# Power.net
KiCad netlist of a schematic drawn in Altium Designer
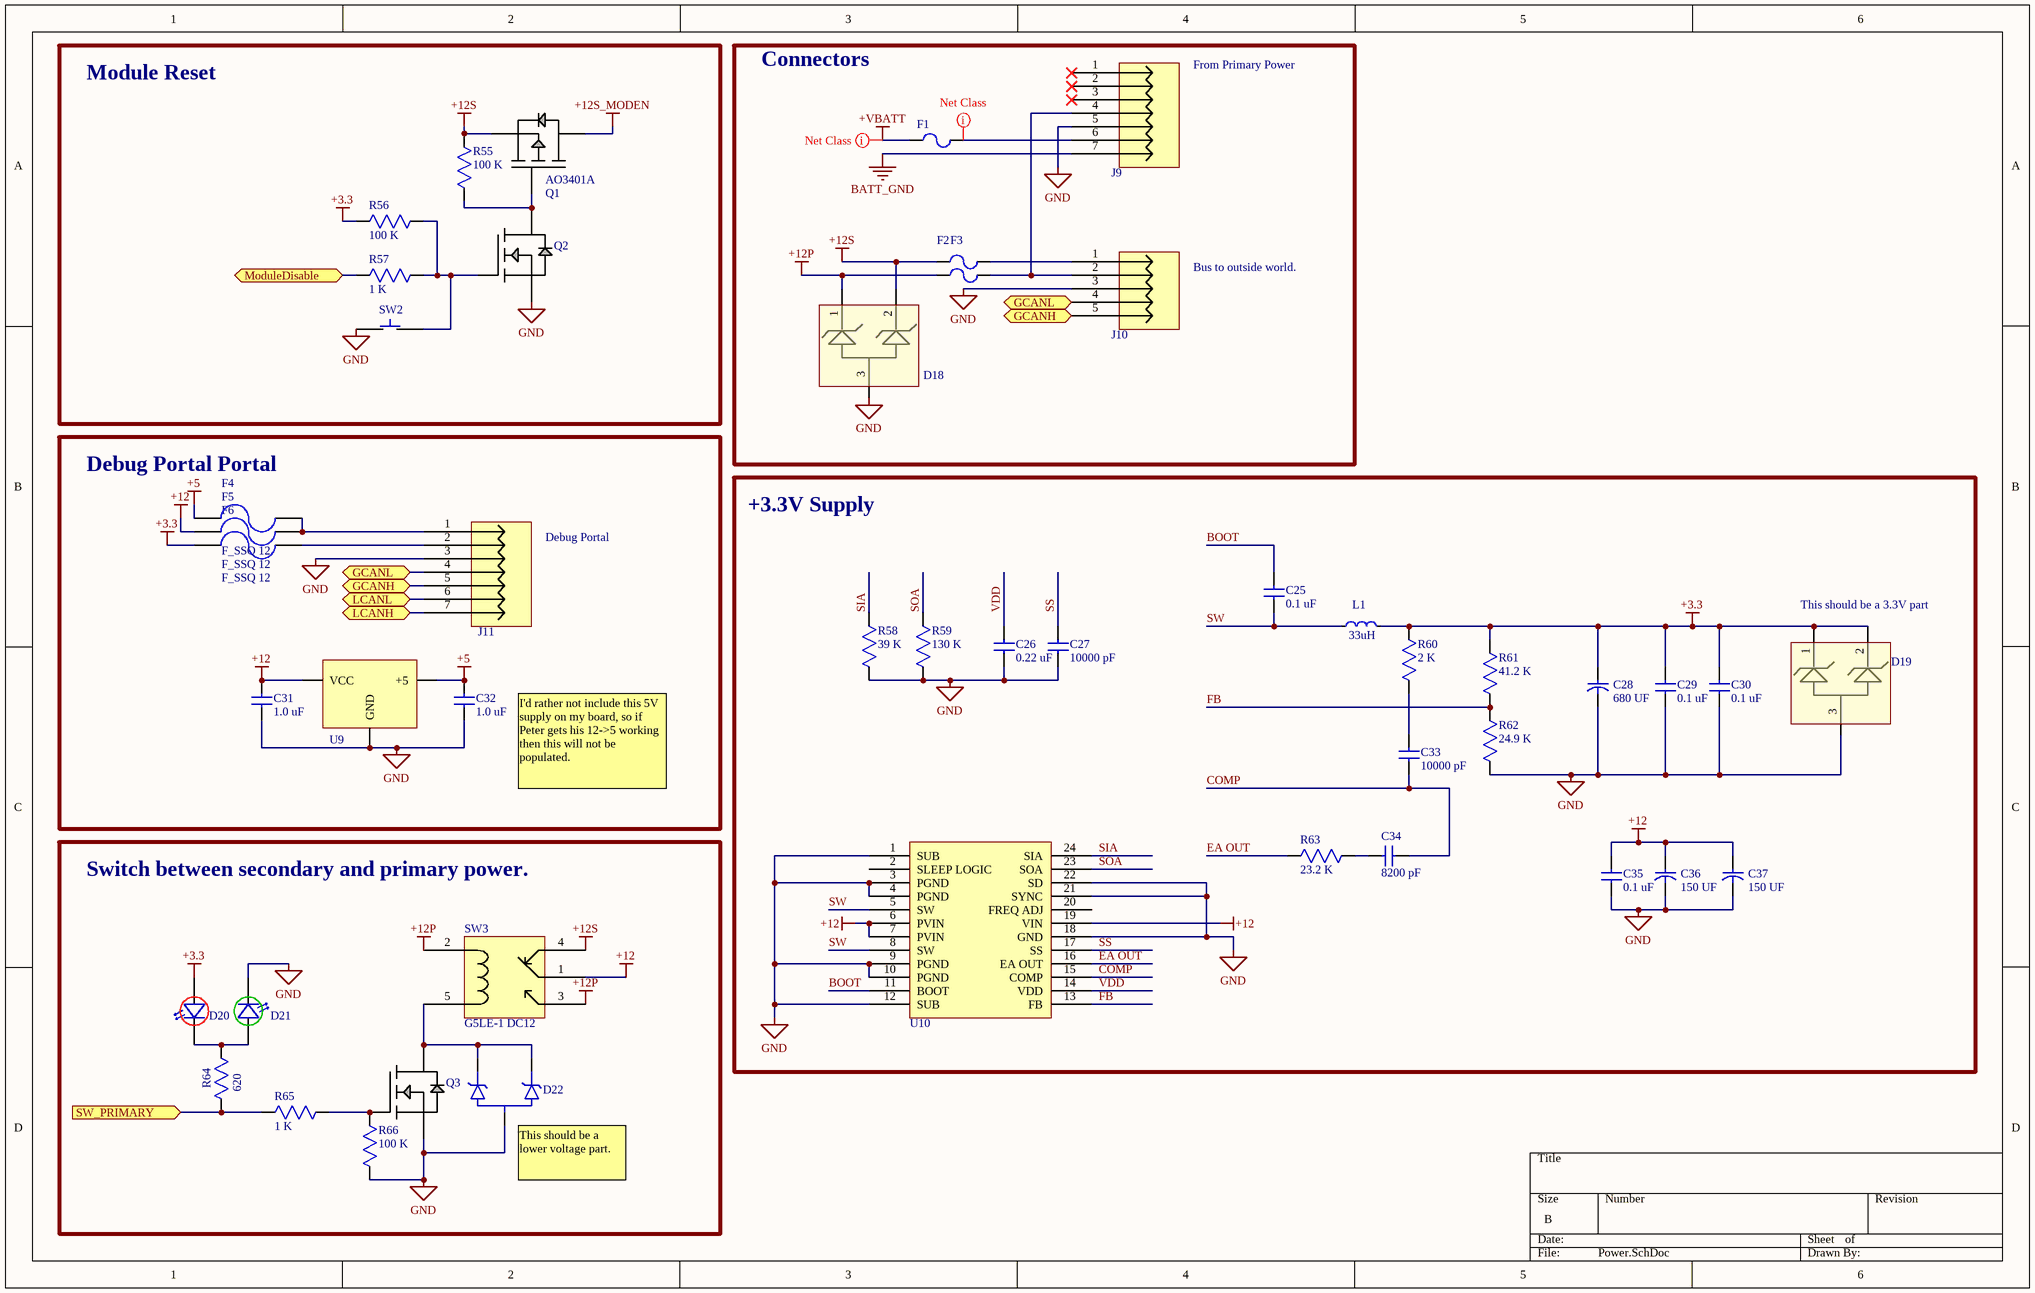
[diagram p0: Power.SchDoc]

(export (version "E")
  (design (tool "Eeschema 10.0.6"))
  (components
    (comp (ref "C25")
      (value "0.1 uF")
      (footprint "0603_cap")
      (description "CAP CERM 0603")
      (fields (field (name "Comment") "CAP 0603"))
      (libsource (lib "Nutz") (part "C_0603"))
    )
    (comp (ref "C26")
      (value "0.22 uF")
      (footprint "0603_cap")
      (description "CAP CERM 0603")
      (fields (field (name "Comment") "CAP 0603"))
      (libsource (lib "Nutz") (part "C_0603"))
    )
    (comp (ref "C27")
      (value "10000 pF")
      (footprint "0603_cap")
      (description "CAP CERM 0603")
      (fields (field (name "Comment") "CAP 0603"))
      (libsource (lib "Nutz") (part "C_0603"))
    )
    (comp (ref "C28")
      (value "680 UF")
      (footprint "CAP_NICHICON_R7")
      (description "CAP POLY 680UF 10V LOW ESR RAD")
      (fields
        (field (name "MANUFACTURER") "Nichicon")
        (field (name "Comment") "CAP POLY 680UF")
        (field (name "SVP CREATOR") "Jonathan Nutzmann")
      )
      (libsource (lib "c3_SchLib") (part "C_POLY_680UF_10V"))
    )
    (comp (ref "C29")
      (value "0.1 uF")
      (footprint "0603_cap")
      (description "CAP CERM 0603")
      (fields (field (name "Comment") "CAP 0603"))
      (libsource (lib "Nutz") (part "C_0603"))
    )
    (comp (ref "C30")
      (value "0.1 uF")
      (footprint "0603_cap")
      (description "CAP CERM 0603")
      (fields (field (name "Comment") "CAP 0603"))
      (libsource (lib "Nutz") (part "C_0603"))
    )
    (comp (ref "C31")
      (value "1.0 uF")
      (footprint "0805_Capacitor")
      (description "CAP CERM 1uF")
      (fields (field (name "Comment") "CAP 1uF") (field (name "SVP CREATOR") "Mark Newcomb"))
      (libsource (lib "c3_SchLib") (part "C_0805_1.0uF"))
    )
    (comp (ref "C32")
      (value "1.0 uF")
      (footprint "0805_Capacitor")
      (description "CAP CERM 1uF")
      (fields (field (name "Comment") "CAP 1uF") (field (name "SVP CREATOR") "Mark Newcomb"))
      (libsource (lib "c3_SchLib") (part "C_0805_1.0uF"))
    )
    (comp (ref "C33")
      (value "10000 pF")
      (footprint "0603_cap")
      (description "CAP CERM 0603")
      (fields (field (name "Comment") "CAP 0603"))
      (libsource (lib "Nutz") (part "C_0603"))
    )
    (comp (ref "C34")
      (value "8200 pF")
      (footprint "0603_cap")
      (description "CAP CERM 0603")
      (fields (field (name "Comment") "CAP 0603"))
      (libsource (lib "Nutz") (part "C_0603"))
    )
    (comp (ref "C35")
      (value "0.1 uF")
      (footprint "0603_cap")
      (description "CAP CERM 0603")
      (fields (field (name "Comment") "CAP 0603"))
      (libsource (lib "Nutz") (part "C_0603"))
    )
    (comp (ref "C36")
      (value "150 UF")
      (footprint "CAP_NICHICON_R7")
      (description "CAP POLY 150UF 20V HT 125C RAD")
      (fields
        (field (name "MANUFACTURER") "Nichicon")
        (field (name "TOLERANCE") "20%")
        (field (name "SVP CREATOR") "Jonathan Nutzmann")
      )
      (libsource (lib "c3_SchLib") (part "C_POLY_150UF"))
    )
    (comp (ref "C37")
      (value "150 UF")
      (footprint "CAP_NICHICON_R7")
      (description "CAP POLY 150UF 20V HT 125C RAD")
      (fields
        (field (name "MANUFACTURER") "Nichicon")
        (field (name "TOLERANCE") "20%")
        (field (name "SVP CREATOR") "Jonathan Nutzmann")
      )
      (libsource (lib "c3_SchLib") (part "C_POLY_150UF"))
    )
    (comp (ref "D18")
      (value "SM15.TCT")
      (footprint "SOT-23")
      (description "IC TVS ARRAY 2UNI/1BI 15V SOT-23")
      (fields (field (name "MANUFACTURER") "Semtech") (field (name "SVP CREATOR") "Jonathan Nutzmann"))
      (libsource (lib "c3_SchLib") (part "D_SM15TCT"))
    )
    (comp (ref "D19")
      (value "MMBZ6V8AL,215")
      (footprint "SOT-23")
      (description "DIODE ESD PROT DBL 4.5V SOT23")
      (fields (field (name "MANUFACTURER") "NXP") (field (name "SVP CREATOR") "Jonathan Nutzmann"))
      (libsource (lib "c3_SchLib") (part "D_MMBZ6V8AL,215"))
    )
    (comp (ref "D20")
      (value "D_LED_0805_RED")
      (footprint "0805P_RED")
      (description "LED CHIPLED 645NM RED DIFF 0805")
      (fields (field (name "SVP CREATOR") "Jonathan Nutzmann"))
      (libsource (lib "c3_SchLib") (part "D_LED_0805_RED"))
    )
    (comp (ref "D21")
      (value "D_LED_0805_GREEN")
      (footprint "0805P_Green")
      (description "LED CHIPLED 570NM GREEN 0805 SMD")
      (fields
        (field (name "MANUFACTURER") "Osram Opto Semiconductors Inc")
        (field (name "SVP CREATOR") "Nate Bolyard")
        (field (name "SVP REVIEWER 1") "Trevtron")
      )
      (libsource (lib "c3_SchLib") (part "D_LED_0805_GREEN"))
    )
    (comp (ref "D22")
      (value "D_AZ23C36-TP")
      (footprint "SOT-23")
      (description "DIODE ZENER DUAL 36V SOT-23")
      (fields (field (name "MANUFACTURER") "Micro") (field (name "SVP CREATOR") "Jonathan Nutzmann"))
      (libsource (lib "c3_SchLib") (part "D_AZ23C36-TP"))
    )
    (comp (ref "F1")
      (value "F_3101.0040")
      (footprint "FPG4 Fuseholder")
      (description "Schurter FPG4 5mm x 20mm Fuse Holder")
      (libsource (lib "c3_SchLib") (part "F_3101.0040"))
    )
    (comp (ref "F2")
      (value "F_3101.0040")
      (footprint "FPG4 Fuseholder")
      (description "Schurter FPG4 5mm x 20mm Fuse Holder")
      (libsource (lib "c3_SchLib") (part "F_3101.0040"))
    )
    (comp (ref "F3")
      (value "F_3101.0040")
      (footprint "FPG4 Fuseholder")
      (description "Schurter FPG4 5mm x 20mm Fuse Holder")
      (libsource (lib "c3_SchLib") (part "F_3101.0040"))
    )
    (comp (ref "F4")
      (value "F_SSQ 12")
      (footprint "2410")
      (description "FUSE 12A 125V 6125 FAST SSQ")
      (fields
        (field (name "MANUFACTURER") "Bel Fuse Inc")
        (field (name "SVN CREATOR") "Nate Bolyard")
        (field (name "SVN REVIEWER 2") "*")
      )
      (libsource (lib "c3_SchLib") (part "F_SSQ 12"))
    )
    (comp (ref "F5")
      (value "F_SSQ 12")
      (footprint "2410")
      (description "FUSE 12A 125V 6125 FAST SSQ")
      (fields
        (field (name "MANUFACTURER") "Bel Fuse Inc")
        (field (name "SVN CREATOR") "Nate Bolyard")
        (field (name "SVN REVIEWER 2") "*")
      )
      (libsource (lib "c3_SchLib") (part "F_SSQ 12"))
    )
    (comp (ref "F6")
      (value "F_SSQ 12")
      (footprint "2410")
      (description "FUSE 12A 125V 6125 FAST SSQ")
      (fields
        (field (name "MANUFACTURER") "Bel Fuse Inc")
        (field (name "SVN CREATOR") "Nate Bolyard")
        (field (name "SVN REVIEWER 2") "*")
      )
      (libsource (lib "c3_SchLib") (part "F_SSQ 12"))
    )
    (comp (ref "J9")
      (value "J_PHOENIX_7M_5.08")
      (footprint "PHONEIX_7_5.08")
      (description "7 Pin Male Phoenix Connector 5.08")
      (fields (field (name "SVP CREATOR") "Jonathan Nutzmann"))
      (libsource (lib "c3_SchLib") (part "J_PHOENIX_7M_5.08"))
    )
    (comp (ref "J10")
      (value "J_PHOENIX_5M_3.5")
      (footprint "1843635")
      (description "5 Pin Male Phoenix Connector 3.5")
      (fields (field (name "SVP CREATOR") "Jonathan Nutzmann"))
      (libsource (lib "c3_SchLib") (part "J_PHOENIX_5M_3.5"))
    )
    (comp (ref "J11")
      (value "~")
      (footprint "1843651")
      (description "7 Pin Male Phoenix Connector 3.5")
      (fields (field (name "SVP CREATOR") "Jonathan Nutzmann"))
      (libsource (lib "c3_SchLib") (part "J_PHOENIX_7M_3.5"))
    )
    (comp (ref "L1")
      (value "33uH")
      (footprint "L_SRR1210")
      (description "INDUCTOR PWR 33UH 20% SHIELD SMD")
      (fields
        (field (name "MANUFACTURER") "Bourns Inc")
        (field (name "Comment") "L_33uH_20%")
        (field (name "SVP CREATOR") "Jonathan Nutzmann")
      )
      (libsource (lib "c3_SchLib") (part "L_33uH_20%"))
    )
    (comp (ref "Q1")
      (value "Q_AO3401A")
      (footprint "SOT-23")
      (description "MOSFET P-CH -30V -4.3A SOT23")
      (fields (field (name "MANUFACTURER") "Alpha & Omega") (field (name "MANUFACTURER PN") "AO3401A"))
      (libsource (lib "Nutz") (part "Q_AO3401A"))
    )
    (comp (ref "Q2")
      (value "RK7002BT116")
      (footprint "SOT-23")
      (description "MOSFET N-CH 60V 250MA SOT-23")
      (fields
        (field (name "MANUFACTURER") "Rohm Semiconductor")
        (field (name "SVP CREATOR") "Jonathan Nutzmann")
      )
      (libsource (lib "c3_SchLib") (part "Q_N_60V_250MA_SOT23"))
    )
    (comp (ref "Q3")
      (value "2SK3541T2L")
      (footprint "SOT-23")
      (description "MOSFET N-CH 20V 0.9A SOT-23")
      (fields
        (field (name "MANUFACTURER") "Fairchild Semiconductor")
        (field (name "SVP CREATOR") "Jonathan Nutzmann")
      )
      (libsource (lib "c3_SchLib") (part "Q_2SK3541T2L"))
    )
    (comp (ref "R55")
      (value "100 K")
      (footprint "0603_res")
      (description "RES 0603")
      (libsource (lib "Nutz") (part "R_0603"))
    )
    (comp (ref "R56")
      (value "100 K")
      (footprint "0603_res")
      (description "RES 0603")
      (libsource (lib "Nutz") (part "R_0603"))
    )
    (comp (ref "R57")
      (value "1 K")
      (footprint "0603_res")
      (description "RES 0603")
      (libsource (lib "Nutz") (part "R_0603"))
    )
    (comp (ref "R58")
      (value "39 K")
      (footprint "0603_res")
      (description "RES 0603")
      (libsource (lib "Nutz") (part "R_0603"))
    )
    (comp (ref "R59")
      (value "130 K")
      (footprint "0603_res")
      (description "RES 0603")
      (libsource (lib "Nutz") (part "R_0603"))
    )
    (comp (ref "R60")
      (value "2 K")
      (footprint "0603_res")
      (description "RES 0603")
      (libsource (lib "Nutz") (part "R_0603"))
    )
    (comp (ref "R61")
      (value "41.2 K")
      (footprint "0603_res")
      (description "RES 0603")
      (libsource (lib "Nutz") (part "R_0603"))
    )
    (comp (ref "R62")
      (value "24.9 K")
      (footprint "0603_res")
      (description "RES 0603")
      (libsource (lib "Nutz") (part "R_0603"))
    )
    (comp (ref "R63")
      (value "23.2 K")
      (footprint "0603_res")
      (description "RES 0603")
      (libsource (lib "Nutz") (part "R_0603"))
    )
    (comp (ref "R64")
      (value "620")
      (footprint "0805_Resistor")
      (description "RES 620 OHM 1/8W 1% 0805 SMD")
      (fields (field (name "Comment") "R_0805_620_1%") (field (name "SVP CREATOR") "Jonathan Nutzmann"))
      (libsource (lib "c3_SchLib") (part "R_0805_620_1%"))
    )
    (comp (ref "R65")
      (value "1 K")
      (footprint "0603_res")
      (description "RES 0603")
      (libsource (lib "Nutz") (part "R_0603"))
    )
    (comp (ref "R66")
      (value "100 K")
      (footprint "0603_res")
      (description "RES 0603")
      (libsource (lib "Nutz") (part "R_0603"))
    )
    (comp (ref "SW2")
      (value "SW_TACT_SWITCH_6x6")
      (footprint "TACT_SWITCH_6x6")
      (description "SWITCH TACT 6MM BLACK 160GF")
      (fields (field (name "MANUFACTURER") "Tyco Electronics") (field (name "SVP CREATOR") "Nate Bolyard"))
      (libsource (lib "c3_SchLib") (part "SW_TACT_SWITCH_6x6"))
    )
    (comp (ref "SW3")
      (value "SW_G5LE-1 DC12")
      (footprint "G5LE-1 DC12")
      (description "RELAY GEN PURPOSE SPDT 10A 12V")
      (fields
        (field (name "MANUFACTURER") "Omron")
        (field (name "MANUFACTURER PN") "G5LE-1 DC12")
        (field (name "SVP CREATOR") "Jonathan Nutzmann")
      )
      (libsource (lib "c3_SchLib") (part "SW_G5LE-1 DC12"))
    )
    (comp (ref "U9")
      (value "MC7805BDTG")
      (footprint "DPAK")
      (description "IC REG POS VOLT 1A 5V DPAK")
      (fields
        (field (name "MANUFACTURER") "ON Semiconductor")
        (field (name "SVP CREATOR") "Jonathan Nutzmann")
      )
      (libsource (lib "c3_SchLib") (part "U_MC7805BDTG"))
    )
    (comp (ref "U10")
      (value "LM2650 DC/DC Converter")
      (footprint "SOIC127P1030X265-24N")
      (description "IC CONVERTER SYNCH DC/DC 24-SOIC")
      (fields
        (field (name "MANUFACTURER") "National Semiconductor")
        (field (name "SVP CREATOR") "Jonathan Nutzmann")
      )
      (libsource (lib "c3_SchLib") (part "U_LM2650"))
    )
  )
  (nets
    (net (code "1") (name "+3.3") (class "Default")
      (node (ref "C28") (pin "1") (pinfunction "1_1") (pintype "passive"))
      (node (ref "C29") (pin "1") (pinfunction "1_1") (pintype "passive"))
      (node (ref "C30") (pin "1") (pinfunction "1_1") (pintype "passive"))
      (node (ref "D19") (pin "1") (pintype "passive"))
      (node (ref "D19") (pin "2") (pintype "passive"))
      (node (ref "D20") (pin "2") (pinfunction "Anode_2") (pintype "passive"))
      (node (ref "F6") (pin "1") (pinfunction "1_1") (pintype "passive"))
      (node (ref "L1") (pin "2") (pinfunction "2_2") (pintype "passive"))
      (node (ref "R56") (pin "2") (pinfunction "2_2") (pintype "passive"))
      (node (ref "R60") (pin "1") (pinfunction "1_1") (pintype "passive"))
      (node (ref "R61") (pin "2") (pinfunction "2_2") (pintype "passive"))
    )
    (net (code "2") (name "+5") (class "Default")
      (node (ref "C32") (pin "1") (pinfunction "1_1") (pintype "passive"))
      (node (ref "F4") (pin "1") (pinfunction "1_1") (pintype "passive"))
      (node (ref "U9") (pin "2") (pinfunction "+5_2") (pintype "passive"))
    )
    (net (code "3") (name "+12") (class "Default")
      (node (ref "C31") (pin "1") (pinfunction "1_1") (pintype "passive"))
      (node (ref "C35") (pin "1") (pinfunction "1_1") (pintype "passive"))
      (node (ref "C36") (pin "1") (pinfunction "1_1") (pintype "passive"))
      (node (ref "C37") (pin "1") (pinfunction "1_1") (pintype "passive"))
      (node (ref "F5") (pin "1") (pinfunction "1_1") (pintype "passive"))
      (node (ref "SW3") (pin "1") (pinfunction "1_1") (pintype "passive"))
      (node (ref "U10") (pin "19") (pinfunction "VIN_19") (pintype "passive"))
      (node (ref "U10") (pin "6") (pinfunction "PVIN_6") (pintype "passive"))
      (node (ref "U10") (pin "7") (pinfunction "PVIN_7") (pintype "passive"))
      (node (ref "U9") (pin "3") (pinfunction "VCC_3") (pintype "passive"))
    )
    (net (code "4") (name "+12P") (class "Default")
      (node (ref "D18") (pin "1") (pintype "passive"))
      (node (ref "F3") (pin "1") (pinfunction "1_1") (pintype "passive"))
      (node (ref "SW3") (pin "2") (pinfunction "+_2") (pintype "passive"))
      (node (ref "SW3") (pin "3") (pinfunction "3_3") (pintype "passive"))
    )
    (net (code "5") (name "+12S") (class "Default")
      (node (ref "D18") (pin "2") (pintype "passive"))
      (node (ref "F2") (pin "1") (pinfunction "1_1") (pintype "passive"))
      (node (ref "Q1") (pin "2") (pinfunction "SOURCE_2") (pintype "passive"))
      (node (ref "R55") (pin "2") (pinfunction "2_2") (pintype "passive"))
      (node (ref "SW3") (pin "4") (pinfunction "4_4") (pintype "passive"))
    )
    (net (code "6") (name "+12S_MODEN") (class "Default")
      (node (ref "Q1") (pin "3") (pinfunction "DRAIN_3") (pintype "passive"))
    )
    (net (code "7") (name "+VBATT") (class "Default")
      (node (ref "F1") (pin "1") (pinfunction "1_1") (pintype "passive"))
    )
    (net (code "8") (name "/BOOT") (class "Default")
      (node (ref "C25") (pin "1") (pinfunction "1_1") (pintype "passive"))
      (node (ref "U10") (pin "11") (pinfunction "BOOT_11") (pintype "passive"))
    )
    (net (code "9") (name "/COMP") (class "Default")
      (node (ref "C33") (pin "2") (pinfunction "2_2") (pintype "passive"))
      (node (ref "C34") (pin "2") (pinfunction "2_2") (pintype "passive"))
      (node (ref "U10") (pin "15") (pinfunction "COMP_15") (pintype "passive"))
    )
    (net (code "10") (name "/EA OUT") (class "Default")
      (node (ref "R63") (pin "2") (pinfunction "2_2") (pintype "passive"))
      (node (ref "U10") (pin "16") (pinfunction "EA_OUT_16") (pintype "passive"))
    )
    (net (code "11") (name "/FB") (class "Default")
      (node (ref "R61") (pin "1") (pinfunction "1_1") (pintype "passive"))
      (node (ref "R62") (pin "2") (pinfunction "2_2") (pintype "passive"))
      (node (ref "U10") (pin "13") (pinfunction "FB_13") (pintype "passive"))
    )
    (net (code "12") (name "/GCANH") (class "Default")
      (node (ref "J10") (pin "5") (pinfunction "5_5") (pintype "passive"))
      (node (ref "J11") (pin "5") (pinfunction "5_5") (pintype "passive"))
    )
    (net (code "13") (name "/GCANL") (class "Default")
      (node (ref "J10") (pin "4") (pinfunction "4_4") (pintype "passive"))
      (node (ref "J11") (pin "4") (pinfunction "4_4") (pintype "passive"))
    )
    (net (code "14") (name "/LCANH") (class "Default")
      (node (ref "J11") (pin "7") (pinfunction "7_7") (pintype "passive"))
    )
    (net (code "15") (name "/LCANL") (class "Default")
      (node (ref "J11") (pin "6") (pinfunction "6_6") (pintype "passive"))
    )
    (net (code "16") (name "/ModuleDisable") (class "Default")
      (node (ref "R57") (pin "2") (pinfunction "2_2") (pintype "passive"))
    )
    (net (code "17") (name "/SIA") (class "Default")
      (node (ref "R58") (pin "1") (pinfunction "1_1") (pintype "passive"))
      (node (ref "U10") (pin "24") (pinfunction "SIA_24") (pintype "passive"))
    )
    (net (code "18") (name "/SOA") (class "Default")
      (node (ref "R59") (pin "1") (pinfunction "1_1") (pintype "passive"))
      (node (ref "U10") (pin "23") (pinfunction "SOA_23") (pintype "passive"))
    )
    (net (code "19") (name "/SS") (class "Default")
      (node (ref "C27") (pin "1") (pinfunction "1_1") (pintype "passive"))
      (node (ref "U10") (pin "17") (pinfunction "SS_17") (pintype "passive"))
    )
    (net (code "20") (name "/SW") (class "Default")
      (node (ref "C25") (pin "2") (pinfunction "2_2") (pintype "passive"))
      (node (ref "L1") (pin "1") (pinfunction "1_1") (pintype "passive"))
      (node (ref "U10") (pin "5") (pinfunction "SW_5") (pintype "passive"))
      (node (ref "U10") (pin "8") (pinfunction "SW_8") (pintype "passive"))
    )
    (net (code "21") (name "/SW_PRIMARY") (class "Default")
      (node (ref "R64") (pin "2") (pinfunction "2_2") (pintype "passive"))
      (node (ref "R65") (pin "2") (pinfunction "2_2") (pintype "passive"))
    )
    (net (code "22") (name "/VDD") (class "Default")
      (node (ref "C26") (pin "1") (pinfunction "1_1") (pintype "passive"))
      (node (ref "U10") (pin "14") (pinfunction "VDD_14") (pintype "passive"))
    )
    (net (code "23") (name "BATT_GND") (class "Default")
      (node (ref "J9") (pin "7") (pinfunction "7_7") (pintype "passive"))
    )
    (net (code "24") (name "GND") (class "Default")
      (node (ref "C26") (pin "2") (pinfunction "2_2") (pintype "passive"))
      (node (ref "C27") (pin "2") (pinfunction "2_2") (pintype "passive"))
      (node (ref "C28") (pin "2") (pinfunction "2_2") (pintype "passive"))
      (node (ref "C29") (pin "2") (pinfunction "2_2") (pintype "passive"))
      (node (ref "C30") (pin "2") (pinfunction "2_2") (pintype "passive"))
      (node (ref "C31") (pin "2") (pinfunction "2_2") (pintype "passive"))
      (node (ref "C32") (pin "2") (pinfunction "2_2") (pintype "passive"))
      (node (ref "C35") (pin "2") (pinfunction "2_2") (pintype "passive"))
      (node (ref "C36") (pin "2") (pinfunction "2_2") (pintype "passive"))
      (node (ref "C37") (pin "2") (pinfunction "2_2") (pintype "passive"))
      (node (ref "D18") (pin "3") (pintype "passive"))
      (node (ref "D19") (pin "3") (pintype "passive"))
      (node (ref "D21") (pin "1") (pinfunction "Cathode_1") (pintype "passive"))
      (node (ref "D22") (pin "3") (pinfunction "ANODE_3") (pintype "passive"))
      (node (ref "J10") (pin "3") (pinfunction "3_3") (pintype "passive"))
      (node (ref "J11") (pin "3") (pinfunction "3_3") (pintype "passive"))
      (node (ref "J9") (pin "5") (pinfunction "5_5") (pintype "passive"))
      (node (ref "Q2") (pin "2") (pinfunction "SOURCE_2") (pintype "passive"))
      (node (ref "Q3") (pin "2") (pinfunction "SOURCE_2") (pintype "passive"))
      (node (ref "R58") (pin "2") (pinfunction "2_2") (pintype "passive"))
      (node (ref "R59") (pin "2") (pinfunction "2_2") (pintype "passive"))
      (node (ref "R62") (pin "1") (pinfunction "1_1") (pintype "passive"))
      (node (ref "R66") (pin "1") (pinfunction "1_1") (pintype "passive"))
      (node (ref "SW2") (pin "1") (pinfunction "1_1") (pintype "passive"))
      (node (ref "U10") (pin "1") (pinfunction "SUB_1") (pintype "passive"))
      (node (ref "U10") (pin "10") (pinfunction "PGND_10") (pintype "passive"))
      (node (ref "U10") (pin "12") (pinfunction "SUB_12") (pintype "passive"))
      (node (ref "U10") (pin "18") (pinfunction "GND_18") (pintype "passive"))
      (node (ref "U10") (pin "21") (pinfunction "SYNC_21") (pintype "passive"))
      (node (ref "U10") (pin "22") (pinfunction "SD_22") (pintype "passive"))
      (node (ref "U10") (pin "3") (pinfunction "PGND_3") (pintype "passive"))
      (node (ref "U10") (pin "4") (pinfunction "PGND_4") (pintype "passive"))
      (node (ref "U10") (pin "9") (pinfunction "PGND_9") (pintype "passive"))
      (node (ref "U9") (pin "1") (pinfunction "GND_1") (pintype "passive"))
    )
    (net (code "25") (name "Net-(C33-Pad1)") (class "Default")
      (node (ref "C33") (pin "1") (pinfunction "1_1") (pintype "passive"))
      (node (ref "R60") (pin "2") (pinfunction "2_2") (pintype "passive"))
    )
    (net (code "26") (name "Net-(C34-Pad1)") (class "Default")
      (node (ref "C34") (pin "1") (pinfunction "1_1") (pintype "passive"))
      (node (ref "R63") (pin "1") (pinfunction "1_1") (pintype "passive"))
    )
    (net (code "27") (name "Net-(D20-Cathode)") (class "Default")
      (node (ref "D20") (pin "1") (pinfunction "Cathode_1") (pintype "passive"))
      (node (ref "D21") (pin "2") (pinfunction "Anode_2") (pintype "passive"))
      (node (ref "R64") (pin "1") (pinfunction "1_1") (pintype "passive"))
    )
    (net (code "28") (name "Net-(D22-CATHODE_1)") (class "Default")
      (node (ref "D22") (pin "1") (pinfunction "CATHODE_1_1") (pintype "passive"))
      (node (ref "D22") (pin "2") (pinfunction "CATHODE_2_2") (pintype "passive"))
      (node (ref "Q3") (pin "3") (pinfunction "DRAIN_3") (pintype "passive"))
      (node (ref "SW3") (pin "5") (pinfunction "-_5") (pintype "passive"))
    )
    (net (code "29") (name "Net-(F1-Pad2)") (class "Default")
      (node (ref "F1") (pin "2") (pinfunction "2_2") (pintype "passive"))
      (node (ref "J9") (pin "6") (pinfunction "6_6") (pintype "passive"))
    )
    (net (code "30") (name "Net-(F2-Pad2)") (class "Default")
      (node (ref "F2") (pin "2") (pinfunction "2_2") (pintype "passive"))
      (node (ref "J10") (pin "1") (pinfunction "1_1") (pintype "passive"))
    )
    (net (code "31") (name "Net-(F3-Pad2)") (class "Default")
      (node (ref "F3") (pin "2") (pinfunction "2_2") (pintype "passive"))
      (node (ref "J10") (pin "2") (pinfunction "2_2") (pintype "passive"))
      (node (ref "J9") (pin "4") (pinfunction "4_4") (pintype "passive"))
    )
    (net (code "32") (name "Net-(F4-Pad2)") (class "Default")
      (node (ref "F4") (pin "2") (pinfunction "2_2") (pintype "passive"))
      (node (ref "F5") (pin "2") (pinfunction "2_2") (pintype "passive"))
      (node (ref "J11") (pin "1") (pinfunction "1_1") (pintype "passive"))
    )
    (net (code "33") (name "Net-(F6-Pad2)") (class "Default")
      (node (ref "F6") (pin "2") (pinfunction "2_2") (pintype "passive"))
      (node (ref "J11") (pin "2") (pinfunction "2_2") (pintype "passive"))
    )
    (net (code "34") (name "Net-(Q1-GATE)") (class "Default")
      (node (ref "Q1") (pin "1") (pinfunction "GATE_1") (pintype "passive"))
      (node (ref "Q2") (pin "3") (pinfunction "DRAIN_3") (pintype "passive"))
      (node (ref "R55") (pin "1") (pinfunction "1_1") (pintype "passive"))
    )
    (net (code "35") (name "Net-(Q2-GATE)") (class "Default")
      (node (ref "Q2") (pin "1") (pinfunction "GATE_1") (pintype "passive"))
      (node (ref "R56") (pin "1") (pinfunction "1_1") (pintype "passive"))
      (node (ref "R57") (pin "1") (pinfunction "1_1") (pintype "passive"))
      (node (ref "SW2") (pin "2") (pinfunction "2_2") (pintype "passive"))
    )
    (net (code "36") (name "Net-(Q3-GATE)") (class "Default")
      (node (ref "Q3") (pin "1") (pinfunction "GATE_1") (pintype "passive"))
      (node (ref "R65") (pin "1") (pinfunction "1_1") (pintype "passive"))
      (node (ref "R66") (pin "2") (pinfunction "2_2") (pintype "passive"))
    )
    (net (code "37") (name "unconnected-(J9-Pad1)") (class "Default")
      (node (ref "J9") (pin "1") (pinfunction "1_1") (pintype "passive+no_connect"))
    )
    (net (code "38") (name "unconnected-(J9-Pad2)") (class "Default")
      (node (ref "J9") (pin "2") (pinfunction "2_2") (pintype "passive+no_connect"))
    )
    (net (code "39") (name "unconnected-(J9-Pad3)") (class "Default")
      (node (ref "J9") (pin "3") (pinfunction "3_3") (pintype "passive+no_connect"))
    )
    (net (code "40") (name "unconnected-(U10-FREQ_ADJ-Pad20)") (class "Default")
      (node (ref "U10") (pin "20") (pinfunction "FREQ_ADJ_20") (pintype "passive"))
    )
    (net (code "41") (name "unconnected-(U10-SLEEP_LOGIC-Pad2)") (class "Default")
      (node (ref "U10") (pin "2") (pinfunction "SLEEP_LOGIC_2") (pintype "passive"))
    )
  )
)
